# Controle.net
KiCad netlist of a schematic drawn in Altium Designer
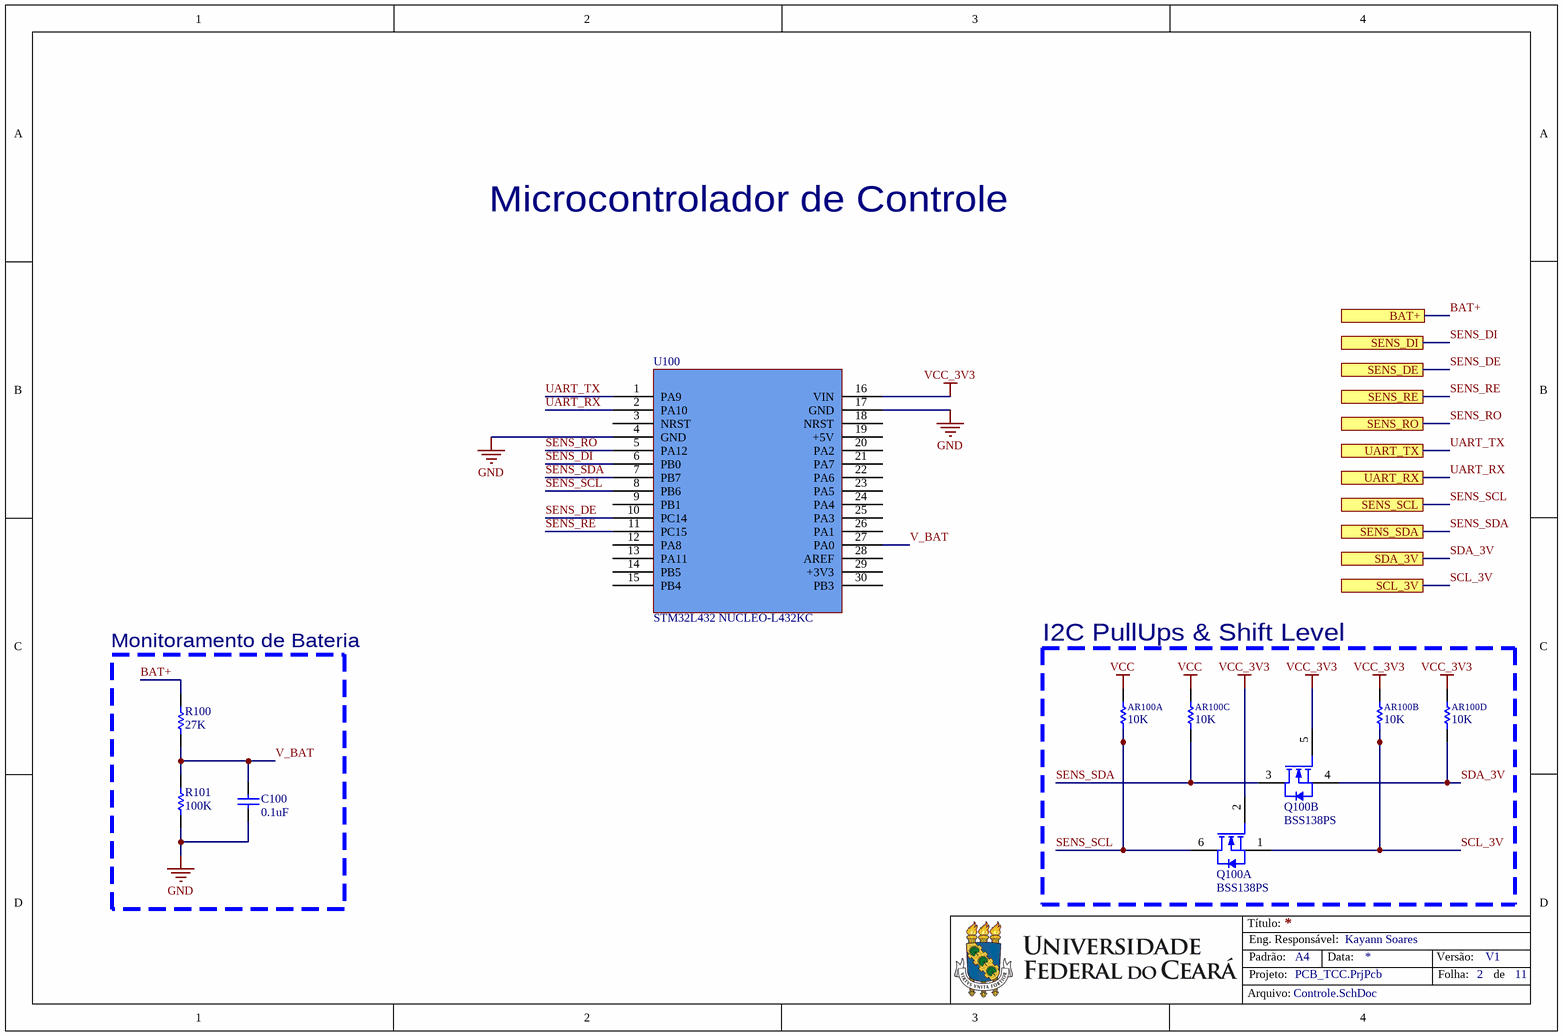
[diagram p0: Controle.SchDoc]

(export (version "E")
  (design (tool "Eeschema 10.0.6"))
  (components
    (comp (ref "AR100")
      (value "10K")
      (footprint "RES_ARRAY _4RES_1206")
      (libsource (lib "PCB_TCC") (part "RES_ARRAY_10K_1206"))
    )
    (comp (ref "C100")
      (value "0.1uF")
      (footprint "CAP_CER_0603")
      (libsource (lib "PCB_TCC") (part "CAP_CER_0.1uF_0603"))
    )
    (comp (ref "Q100")
      (value "BSS138PS")
      (footprint "BSS138PS")
      (libsource (lib "PCB_TCC") (part "BSS138PS"))
    )
    (comp (ref "R100") (value "27K") (footprint "RES_0603") (libsource (lib "PCB_TCC") (part "RES_27K_0603")))
    (comp (ref "R101")
      (value "100K")
      (footprint "RES_0603")
      (libsource (lib "PCB_TCC") (part "RES_100K_0603"))
    )
    (comp (ref "U100")
      (value "STM32L432 NUCLEO-L432KC")
      (footprint "STM32L432")
      (libsource (lib "PCB_TCC") (part "STM32L432"))
    )
  )
  (nets
    (net (code "1") (name "/BAT+") (class "Default")
      (node (ref "R100") (pin "2") (pinfunction "2_2") (pintype "passive"))
    )
    (net (code "2") (name "/SCL_3V") (class "Default")
      (node (ref "AR100") (pin "2") (pinfunction "2_2") (pintype "passive"))
      (node (ref "Q100") (pin "1") (pinfunction "S1_1") (pintype "passive"))
    )
    (net (code "3") (name "/SDA_3V") (class "Default")
      (node (ref "AR100") (pin "4") (pinfunction "4_4") (pintype "passive"))
      (node (ref "Q100") (pin "4") (pinfunction "S2_4") (pintype "passive"))
    )
    (net (code "4") (name "/SENS_DE") (class "Default")
      (node (ref "U100") (pin "10") (pinfunction "PC14_10") (pintype "passive"))
    )
    (net (code "5") (name "/SENS_DI") (class "Default")
      (node (ref "U100") (pin "6") (pinfunction "PB0_6") (pintype "passive"))
    )
    (net (code "6") (name "/SENS_RE") (class "Default")
      (node (ref "U100") (pin "11") (pinfunction "PC15_11") (pintype "passive"))
    )
    (net (code "7") (name "/SENS_RO") (class "Default")
      (node (ref "U100") (pin "5") (pinfunction "PA12_5") (pintype "passive"))
    )
    (net (code "8") (name "/SENS_SCL") (class "Default")
      (node (ref "AR100") (pin "1") (pinfunction "1_1") (pintype "passive"))
      (node (ref "Q100") (pin "6") (pinfunction "D1_6") (pintype "passive"))
      (node (ref "U100") (pin "8") (pinfunction "PB6_8") (pintype "passive"))
    )
    (net (code "9") (name "/SENS_SDA") (class "Default")
      (node (ref "AR100") (pin "3") (pinfunction "3_3") (pintype "passive"))
      (node (ref "Q100") (pin "3") (pinfunction "D2_3") (pintype "passive"))
      (node (ref "U100") (pin "7") (pinfunction "PB7_7") (pintype "passive"))
    )
    (net (code "10") (name "/UART_RX") (class "Default")
      (node (ref "U100") (pin "2") (pinfunction "PA10_2") (pintype "passive"))
    )
    (net (code "11") (name "/UART_TX") (class "Default")
      (node (ref "U100") (pin "1") (pinfunction "PA9_1") (pintype "passive"))
    )
    (net (code "12") (name "/V_BAT") (class "Default")
      (node (ref "C100") (pin "2") (pinfunction "2_2") (pintype "passive"))
      (node (ref "R100") (pin "1") (pinfunction "1_1") (pintype "passive"))
      (node (ref "R101") (pin "2") (pinfunction "2_2") (pintype "passive"))
      (node (ref "U100") (pin "27") (pinfunction "PA0_27") (pintype "passive"))
    )
    (net (code "13") (name "GND") (class "Default")
      (node (ref "C100") (pin "1") (pinfunction "1_1") (pintype "passive"))
      (node (ref "R101") (pin "1") (pinfunction "1_1") (pintype "passive"))
      (node (ref "U100") (pin "17") (pinfunction "GND_17") (pintype "passive"))
      (node (ref "U100") (pin "4") (pinfunction "GND_4") (pintype "passive"))
    )
    (net (code "14") (name "VCC") (class "Default")
      (node (ref "AR100") (pin "6") (pinfunction "6_6") (pintype "passive"))
      (node (ref "AR100") (pin "8") (pinfunction "8_8") (pintype "passive"))
    )
    (net (code "15") (name "VCC_3V3") (class "Default")
      (node (ref "AR100") (pin "5") (pinfunction "5_5") (pintype "passive"))
      (node (ref "AR100") (pin "7") (pinfunction "7_7") (pintype "passive"))
      (node (ref "Q100") (pin "2") (pinfunction "G1_2") (pintype "passive"))
      (node (ref "Q100") (pin "5") (pinfunction "G2_5") (pintype "passive"))
      (node (ref "U100") (pin "16") (pinfunction "VIN_16") (pintype "passive"))
    )
    (net (code "16") (name "unconnected-(U100-+3V3-Pad29)") (class "Default")
      (node (ref "U100") (pin "29") (pinfunction "+3V3_29") (pintype "passive"))
    )
    (net (code "17") (name "unconnected-(U100-+5V-Pad19)") (class "Default")
      (node (ref "U100") (pin "19") (pinfunction "+5V_19") (pintype "passive"))
    )
    (net (code "18") (name "unconnected-(U100-AREF-Pad28)") (class "Default")
      (node (ref "U100") (pin "28") (pinfunction "AREF_28") (pintype "passive"))
    )
    (net (code "19") (name "unconnected-(U100-NRST-Pad3)") (class "Default")
      (node (ref "U100") (pin "3") (pinfunction "NRST_3") (pintype "passive"))
    )
    (net (code "20") (name "unconnected-(U100-NRST-Pad18)") (class "Default")
      (node (ref "U100") (pin "18") (pinfunction "NRST_18") (pintype "passive"))
    )
    (net (code "21") (name "unconnected-(U100-PA1-Pad26)") (class "Default")
      (node (ref "U100") (pin "26") (pinfunction "PA1_26") (pintype "passive"))
    )
    (net (code "22") (name "unconnected-(U100-PA2-Pad20)") (class "Default")
      (node (ref "U100") (pin "20") (pinfunction "PA2_20") (pintype "passive"))
    )
    (net (code "23") (name "unconnected-(U100-PA3-Pad25)") (class "Default")
      (node (ref "U100") (pin "25") (pinfunction "PA3_25") (pintype "passive"))
    )
    (net (code "24") (name "unconnected-(U100-PA4-Pad24)") (class "Default")
      (node (ref "U100") (pin "24") (pinfunction "PA4_24") (pintype "passive"))
    )
    (net (code "25") (name "unconnected-(U100-PA5-Pad23)") (class "Default")
      (node (ref "U100") (pin "23") (pinfunction "PA5_23") (pintype "passive"))
    )
    (net (code "26") (name "unconnected-(U100-PA6-Pad22)") (class "Default")
      (node (ref "U100") (pin "22") (pinfunction "PA6_22") (pintype "passive"))
    )
    (net (code "27") (name "unconnected-(U100-PA7-Pad21)") (class "Default")
      (node (ref "U100") (pin "21") (pinfunction "PA7_21") (pintype "passive"))
    )
    (net (code "28") (name "unconnected-(U100-PA8-Pad12)") (class "Default")
      (node (ref "U100") (pin "12") (pinfunction "PA8_12") (pintype "passive"))
    )
    (net (code "29") (name "unconnected-(U100-PA11-Pad13)") (class "Default")
      (node (ref "U100") (pin "13") (pinfunction "PA11_13") (pintype "passive"))
    )
    (net (code "30") (name "unconnected-(U100-PB1-Pad9)") (class "Default")
      (node (ref "U100") (pin "9") (pinfunction "PB1_9") (pintype "passive"))
    )
    (net (code "31") (name "unconnected-(U100-PB3-Pad30)") (class "Default")
      (node (ref "U100") (pin "30") (pinfunction "PB3_30") (pintype "passive"))
    )
    (net (code "32") (name "unconnected-(U100-PB4-Pad15)") (class "Default")
      (node (ref "U100") (pin "15") (pinfunction "PB4_15") (pintype "passive"))
    )
    (net (code "33") (name "unconnected-(U100-PB5-Pad14)") (class "Default")
      (node (ref "U100") (pin "14") (pinfunction "PB5_14") (pintype "passive"))
    )
  )
)
